# espwithDRV2880.net
KiCad netlist of a schematic drawn in EasyEDA
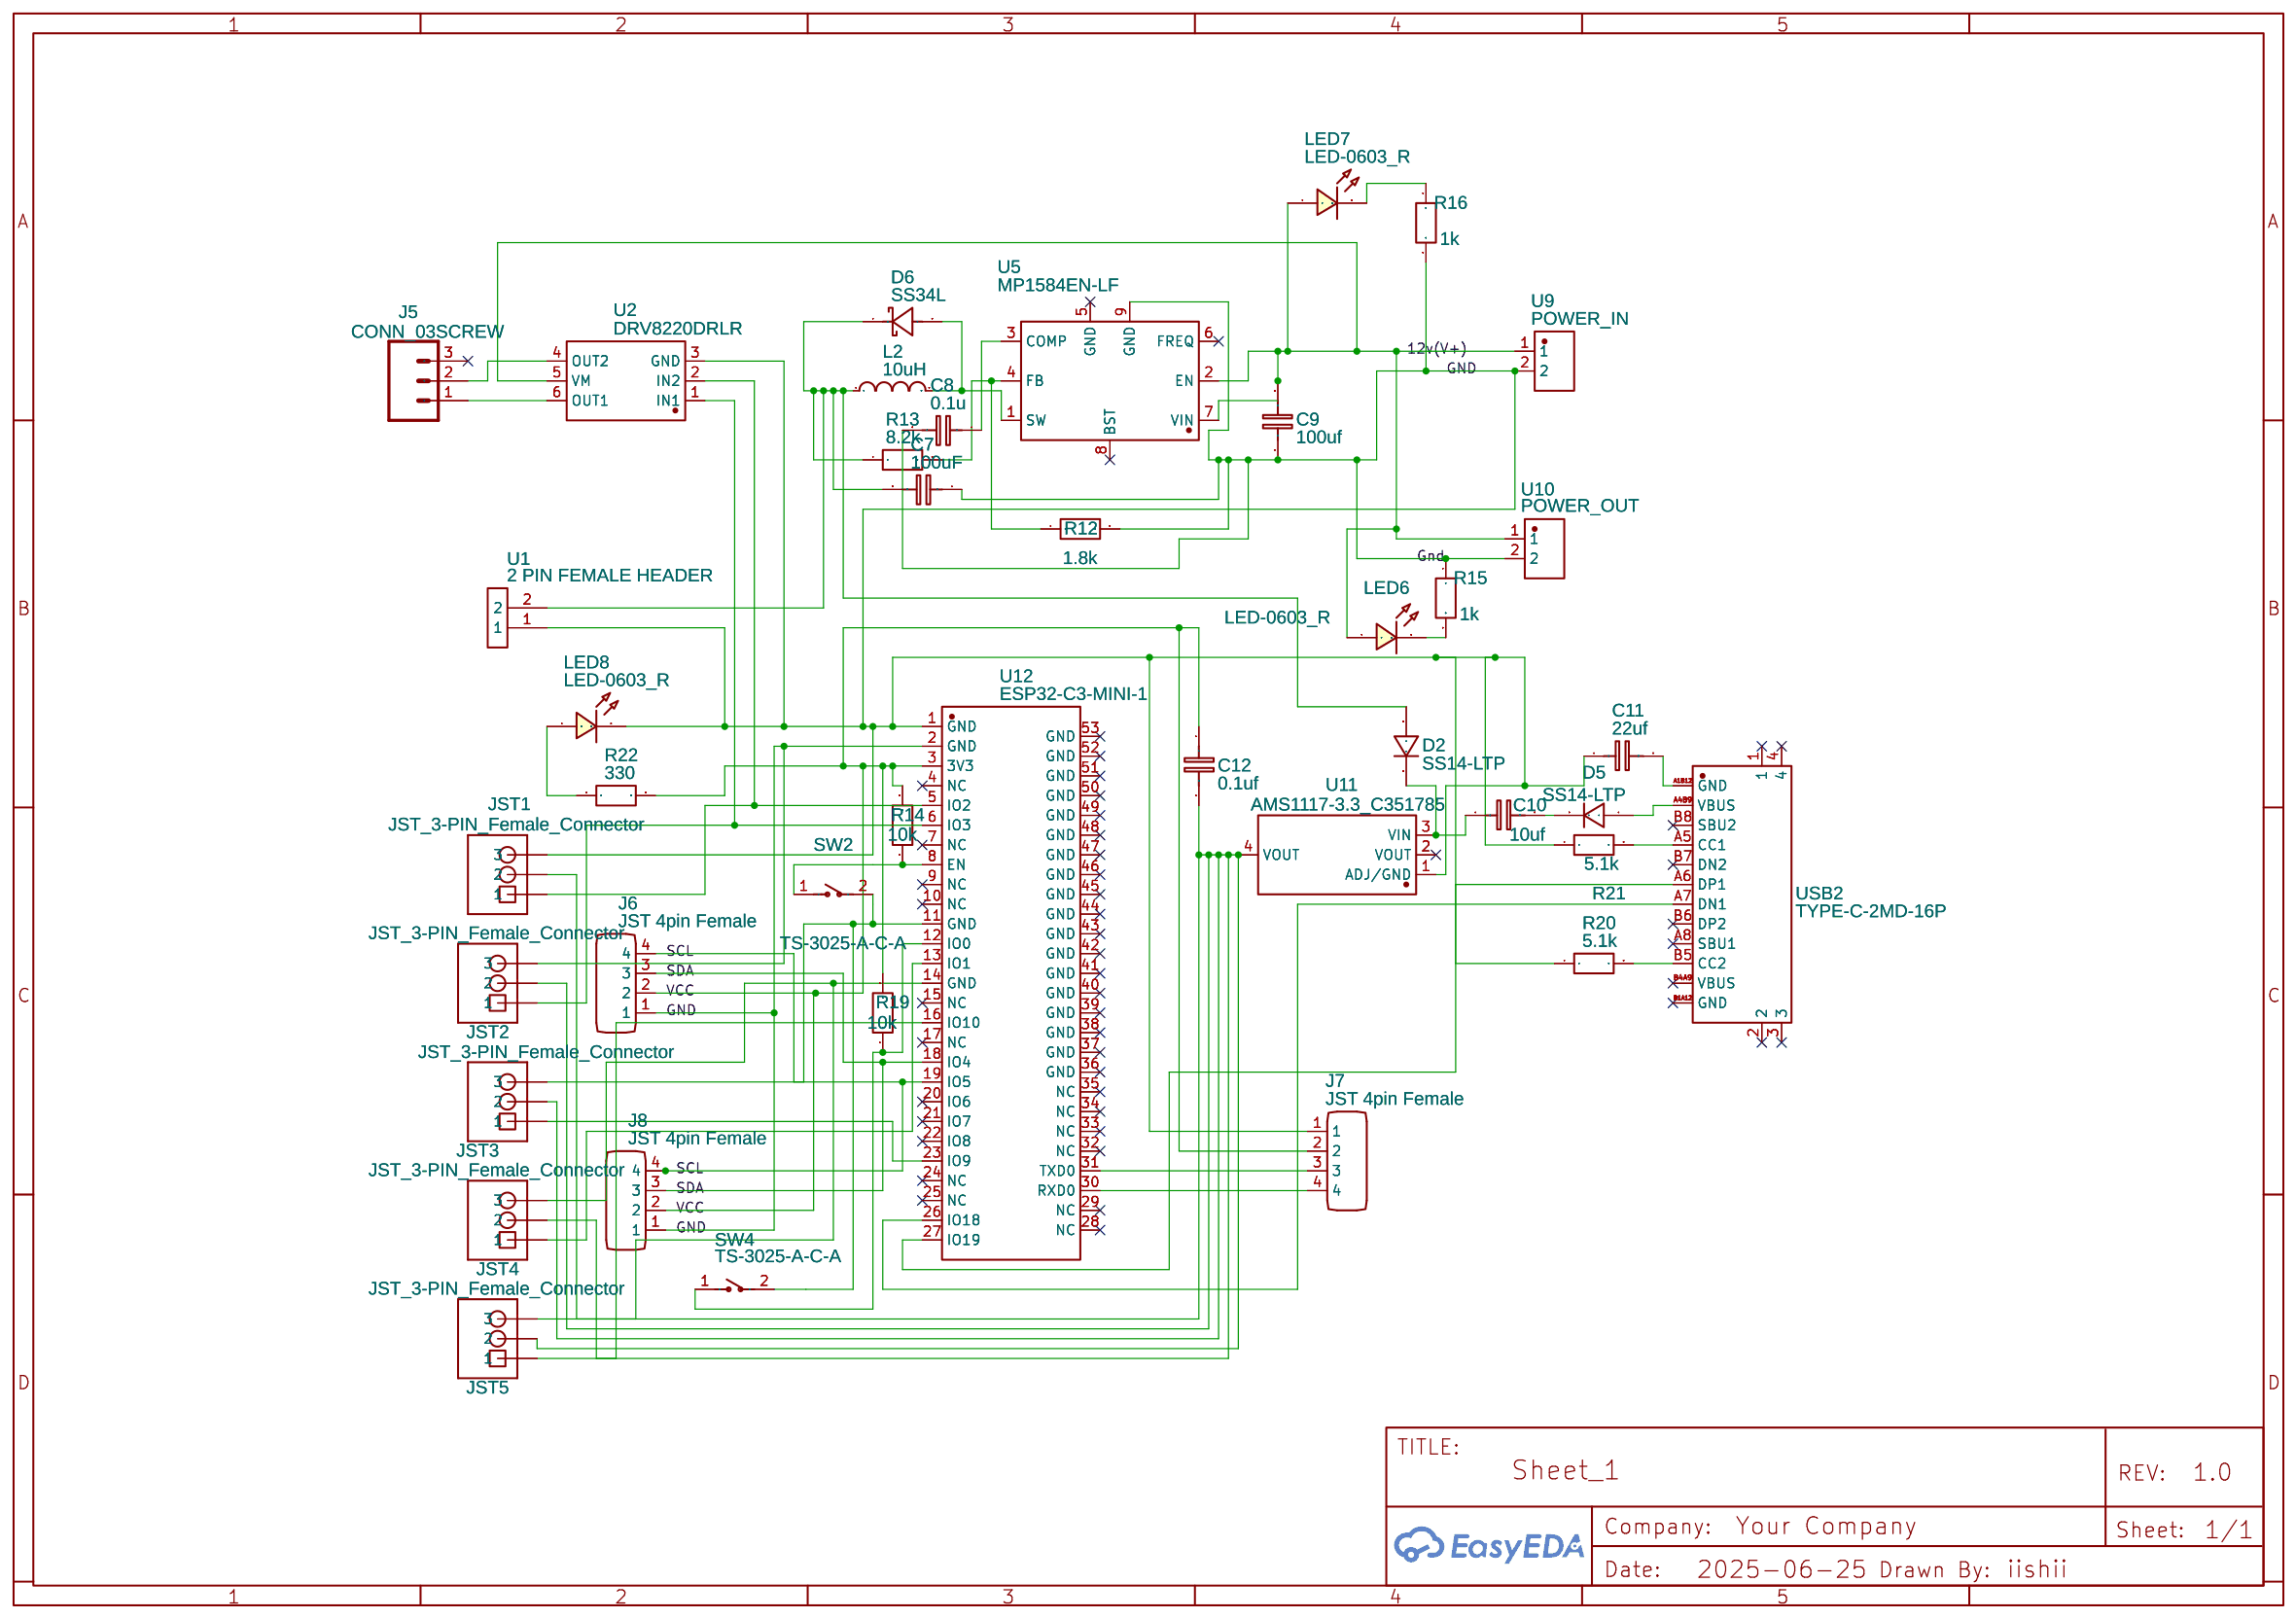
[diagram p0: schematic sheet]

(export (version "E")
  (design (tool "Eeschema 10.0.6"))
  (components
    (comp (ref "C7") (value "100uF") (libsource (lib "") (part "C_0603_EU")))
    (comp (ref "C8") (value "0.1u") (libsource (lib "") (part "C_0603_EU")))
    (comp (ref "C9") (value "100uf") (libsource (lib "") (part "C_0603_EU_2")))
    (comp (ref "C10") (value "10uf") (libsource (lib "") (part "C_0603_EU_1")))
    (comp (ref "C11") (value "22uf") (libsource (lib "") (part "C_0603_EU_1")))
    (comp (ref "C12") (value "0.1uf") (libsource (lib "") (part "C_0603_EU_3")))
    (comp (ref "D2")
      (value "SS14-LTP")
      (fields (field (name "Manufacturer") "MCC(美微科)"))
      (libsource (lib "") (part "SS14-LTP_1"))
    )
    (comp (ref "D5")
      (value "SS14-LTP")
      (fields (field (name "Manufacturer") "MCC(美微科)"))
      (libsource (lib "") (part "SS14-LTP"))
    )
    (comp (ref "D6")
      (value "SS34L")
      (fields (field (name "Manufacturer") "Hottech(合科泰)"))
      (libsource (lib "") (part "SS34L"))
    )
    (comp (ref "J5") (value "CONN_03SCREW") (libsource (lib "") (part "CONN_03SCREW")))
    (comp (ref "J6") (value "JST 4pin Female") (libsource (lib "") (part "JST 4pin Female")))
    (comp (ref "J7") (value "JST 4pin Female") (libsource (lib "") (part "JST 4pin Female_1")))
    (comp (ref "J8") (value "JST 4pin Female") (libsource (lib "") (part "JST 4pin Female")))
    (comp (ref "JST1")
      (value "JST_3-PIN_Female_Connector")
      (libsource (lib "") (part "JST_3-PIN_Female_Connector"))
    )
    (comp (ref "JST2")
      (value "JST_3-PIN_Female_Connector")
      (libsource (lib "") (part "JST_3-PIN_Female_Connector"))
    )
    (comp (ref "JST3")
      (value "JST_3-PIN_Female_Connector")
      (libsource (lib "") (part "JST_3-PIN_Female_Connector"))
    )
    (comp (ref "JST4")
      (value "JST_3-PIN_Female_Connector")
      (libsource (lib "") (part "JST_3-PIN_Female_Connector"))
    )
    (comp (ref "JST5")
      (value "JST_3-PIN_Female_Connector")
      (libsource (lib "") (part "JST_3-PIN_Female_Connector"))
    )
    (comp (ref "L2") (value "10uH") (libsource (lib "") (part "L0603_US")))
    (comp (ref "LED6")
      (value "LED-0603_R")
      (fields
        (field (name "Manufacturer Part") "19-217/R6C-AL1M2VY/3T")
        (field (name "Manufacturer") "EVERLIGHT(台湾亿光)")
      )
      (libsource (lib "") (part "LED-0603_R"))
    )
    (comp (ref "LED7")
      (value "LED-0603_R")
      (fields
        (field (name "Manufacturer Part") "19-217/R6C-AL1M2VY/3T")
        (field (name "Manufacturer") "EVERLIGHT(台湾亿光)")
      )
      (libsource (lib "") (part "LED-0603_R"))
    )
    (comp (ref "LED8")
      (value "LED-0603_R")
      (fields
        (field (name "Manufacturer Part") "19-217/R6C-AL1M2VY/3T")
        (field (name "Manufacturer") "EVERLIGHT(台湾亿光)")
      )
      (libsource (lib "") (part "LED-0603_R"))
    )
    (comp (ref "R12") (value "1.8k") (libsource (lib "") (part "R_0603_EU_2")))
    (comp (ref "R13") (value "8.2k") (libsource (lib "") (part "R_0603_EU_2")))
    (comp (ref "R14") (value "10k") (libsource (lib "") (part "R_0603_EU_1")))
    (comp (ref "R15") (value "1k") (libsource (lib "") (part "R_0603_EU")))
    (comp (ref "R16") (value "1k") (libsource (lib "") (part "R_0603_EU")))
    (comp (ref "R19") (value "10k") (libsource (lib "") (part "R_0603_EU_1")))
    (comp (ref "R20") (value "5.1k") (libsource (lib "") (part "R_0603_EU_2")))
    (comp (ref "R21") (value "5.1k") (libsource (lib "") (part "R_0603_EU_2")))
    (comp (ref "R22") (value "330") (libsource (lib "") (part "R_0603_EU_2")))
    (comp (ref "SW2")
      (value "TS-3025-A-C-A")
      (fields (field (name "Manufacturer") "XKB Connection(中国星坤)"))
      (libsource (lib "") (part "TS-3025-A-C-A"))
    )
    (comp (ref "SW4")
      (value "TS-3025-A-C-A")
      (fields (field (name "Manufacturer") "XKB Connection(中国星坤)"))
      (libsource (lib "") (part "TS-3025-A-C-A"))
    )
    (comp (ref "U1")
      (value "2 PIN FEMALE HEADER")
      (fields (field (name "Manufacturer Part") "4 Pin Female Header"))
      (libsource (lib "") (part "2 PIN FEMALE HEADER"))
    )
    (comp (ref "U2")
      (value "DRV8220DRLR")
      (fields (field (name "Manufacturer") "TI(德州仪器)"))
      (libsource (lib "") (part "DRV8220DRLR"))
    )
    (comp (ref "U5")
      (value "MP1584EN-LF")
      (fields (field (name "Manufacturer") "MPS(芯源)"))
      (libsource (lib "") (part "MP1584EN-LF"))
    )
    (comp (ref "U9")
      (value "POWER_IN")
      (fields (field (name "Manufacturer Part") "JST-B2PS-VH(LF)(SN)黑色"))
      (libsource (lib "") (part "JST-B2PS-VH(LF)(SN)黑色"))
    )
    (comp (ref "U10")
      (value "POWER_OUT")
      (fields (field (name "Manufacturer Part") "JST-B2PS-VH(LF)(SN)黑色"))
      (libsource (lib "") (part "JST-B2PS-VH(LF)(SN)黑色"))
    )
    (comp (ref "U11")
      (value "AMS1117-3.3_C351785")
      (fields (field (name "Manufacturer Part") "AMS1117-3.3") (field (name "Manufacturer") "PUOLOP(迪浦)"))
      (libsource (lib "") (part "AMS1117-3.3_C351785"))
    )
    (comp (ref "U12")
      (value "ESP32-C3-MINI-1")
      (fields (field (name "Manufacturer") "RF Crazy(智汉)"))
      (libsource (lib "") (part "ESP32-C3-MINI-1"))
    )
    (comp (ref "USB2")
      (value "TYPE-C-2MD-16P")
      (fields (field (name "Manufacturer") "JXTCONN(聚兴泰)"))
      (libsource (lib "") (part "TYPE-C-2MD-16P"))
    )
  )
  (nets
    (net (code "1") (name "/12v(V+)") (class "Default")
      (node (ref "C9") (pin "2") (pinfunction "2_2") (pintype "unspecified"))
      (node (ref "LED6") (pin "1") (pinfunction "1_1") (pintype "unspecified"))
      (node (ref "LED7") (pin "1") (pinfunction "1_1") (pintype "unspecified"))
      (node (ref "U10") (pin "1") (pinfunction "1_1") (pintype "unspecified"))
      (node (ref "U2") (pin "5") (pinfunction "VM_5") (pintype "unspecified"))
      (node (ref "U5") (pin "2") (pinfunction "EN_2") (pintype "unspecified"))
      (node (ref "U5") (pin "7") (pinfunction "VIN_7") (pintype "unspecified"))
      (node (ref "U9") (pin "1") (pinfunction "1_1") (pintype "unspecified"))
    )
    (net (code "2") (name "/GND") (class "Default")
      (node (ref "C11") (pin "1") (pinfunction "1_1") (pintype "unspecified"))
      (node (ref "C7") (pin "1") (pinfunction "1_1") (pintype "unspecified"))
      (node (ref "C8") (pin "2") (pinfunction "2_2") (pintype "unspecified"))
      (node (ref "C9") (pin "1") (pinfunction "1_1") (pintype "unspecified"))
      (node (ref "J6") (pin "1") (pinfunction "1_1") (pintype "unspecified"))
      (node (ref "J7") (pin "1") (pinfunction "1_1") (pintype "unspecified"))
      (node (ref "J8") (pin "1") (pinfunction "1_1") (pintype "unspecified"))
      (node (ref "JST1") (pin "3") (pinfunction "3_3") (pintype "unspecified"))
      (node (ref "JST2") (pin "3") (pinfunction "3_3") (pintype "unspecified"))
      (node (ref "LED8") (pin "2") (pinfunction "2_2") (pintype "unspecified"))
      (node (ref "R12") (pin "2") (pinfunction "2_2") (pintype "unspecified"))
      (node (ref "R15") (pin "1") (pinfunction "1_1") (pintype "unspecified"))
      (node (ref "R16") (pin "2") (pinfunction "2_2") (pintype "unspecified"))
      (node (ref "R20") (pin "1") (pinfunction "1_1") (pintype "unspecified"))
      (node (ref "R21") (pin "1") (pinfunction "1_1") (pintype "unspecified"))
      (node (ref "U1") (pin "1") (pinfunction "1_1") (pintype "unspecified"))
      (node (ref "U10") (pin "2") (pinfunction "2_2") (pintype "unspecified"))
      (node (ref "U11") (pin "1") (pinfunction "ADJ/GND_1") (pintype "unspecified"))
      (node (ref "U12") (pin "1") (pinfunction "GND_1") (pintype "unspecified"))
      (node (ref "U12") (pin "2") (pinfunction "GND_2") (pintype "unspecified"))
      (node (ref "U2") (pin "3") (pinfunction "GND_3") (pintype "unspecified"))
      (node (ref "U5") (pin "9") (pinfunction "GND_9") (pintype "unspecified"))
      (node (ref "U9") (pin "2") (pinfunction "2_2") (pintype "unspecified"))
    )
    (net (code "3") (name "/SCL") (class "Default")
      (node (ref "J6") (pin "4") (pinfunction "4_4") (pintype "unspecified"))
      (node (ref "J8") (pin "4") (pinfunction "4_4") (pintype "unspecified"))
      (node (ref "U12") (pin "19") (pinfunction "IO5_19") (pintype "unspecified"))
    )
    (net (code "4") (name "/SDA") (class "Default")
      (node (ref "J6") (pin "3") (pinfunction "3_3") (pintype "unspecified"))
      (node (ref "J8") (pin "3") (pinfunction "3_3") (pintype "unspecified"))
      (node (ref "U12") (pin "18") (pinfunction "IO4_18") (pintype "unspecified"))
    )
    (net (code "5") (name "/VCC") (class "Default")
      (node (ref "C12") (pin "1") (pinfunction "1_1") (pintype "unspecified"))
      (node (ref "J6") (pin "2") (pinfunction "2_2") (pintype "unspecified"))
      (node (ref "J7") (pin "2") (pinfunction "2_2") (pintype "unspecified"))
      (node (ref "J8") (pin "2") (pinfunction "2_2") (pintype "unspecified"))
      (node (ref "R14") (pin "2") (pinfunction "2_2") (pintype "unspecified"))
      (node (ref "R19") (pin "2") (pinfunction "2_2") (pintype "unspecified"))
      (node (ref "R22") (pin "2") (pinfunction "2_2") (pintype "unspecified"))
      (node (ref "U12") (pin "3") (pinfunction "3V3_3") (pintype "unspecified"))
    )
    (net (code "6") (name "Net-(C11-Pad2)") (class "Default")
      (node (ref "C11") (pin "2") (pinfunction "2_2") (pintype "unspecified"))
      (node (ref "USB2") (pin "A1B12") (pinfunction "GND_A1B12") (pintype "unspecified"))
    )
    (net (code "7") (name "Net-(C12-Pad2)") (class "Default")
      (node (ref "C12") (pin "2") (pinfunction "2_2") (pintype "unspecified"))
      (node (ref "JST1") (pin "2") (pinfunction "2_2") (pintype "unspecified"))
      (node (ref "JST2") (pin "2") (pinfunction "2_2") (pintype "unspecified"))
      (node (ref "JST3") (pin "2") (pinfunction "2_2") (pintype "unspecified"))
      (node (ref "JST4") (pin "2") (pinfunction "2_2") (pintype "unspecified"))
      (node (ref "JST5") (pin "2") (pinfunction "2_2") (pintype "unspecified"))
      (node (ref "U11") (pin "4") (pinfunction "VOUT_4") (pintype "unspecified"))
    )
    (net (code "8") (name "Net-(D2-A)") (class "Default")
      (node (ref "C7") (pin "2") (pinfunction "2_2") (pintype "unspecified"))
      (node (ref "D2") (pin "1") (pinfunction "A_1") (pintype "unspecified"))
      (node (ref "D6") (pin "1") (pinfunction "C_1") (pintype "unspecified"))
      (node (ref "L2") (pin "1") (pinfunction "1_1") (pintype "unspecified"))
      (node (ref "R13") (pin "1") (pinfunction "1_1") (pintype "unspecified"))
      (node (ref "U1") (pin "2") (pinfunction "2_2") (pintype "unspecified"))
    )
    (net (code "9") (name "Net-(D2-K)") (class "Default")
      (node (ref "C10") (pin "1") (pinfunction "1_1") (pintype "unspecified"))
      (node (ref "D2") (pin "2") (pinfunction "K_2") (pintype "unspecified"))
      (node (ref "U11") (pin "3") (pinfunction "VIN_3") (pintype "unspecified"))
    )
    (net (code "10") (name "Net-(D5-A)") (class "Default")
      (node (ref "D5") (pin "1") (pinfunction "A_1") (pintype "unspecified"))
      (node (ref "USB2") (pin "A4B9") (pinfunction "VBUS_A4B9") (pintype "unspecified"))
    )
    (net (code "11") (name "Net-(D5-K)") (class "Default")
      (node (ref "C10") (pin "2") (pinfunction "2_2") (pintype "unspecified"))
      (node (ref "D5") (pin "2") (pinfunction "K_2") (pintype "unspecified"))
    )
    (net (code "12") (name "Net-(D6-A)") (class "Default")
      (node (ref "D6") (pin "2") (pinfunction "A_2") (pintype "unspecified"))
      (node (ref "L2") (pin "2") (pinfunction "2_2") (pintype "unspecified"))
      (node (ref "U5") (pin "1") (pinfunction "SW_1") (pintype "unspecified"))
    )
    (net (code "13") (name "Net-(JST3-Pad3)") (class "Default")
      (node (ref "JST3") (pin "3") (pinfunction "3_3") (pintype "unspecified"))
      (node (ref "SW2") (pin "2") (pinfunction "2_2") (pintype "unspecified"))
      (node (ref "SW4") (pin "2") (pinfunction "2_2") (pintype "unspecified"))
      (node (ref "U12") (pin "11") (pinfunction "GND_11") (pintype "unspecified"))
    )
    (net (code "14") (name "Net-(JST4-Pad3)") (class "Default")
      (node (ref "JST4") (pin "3") (pinfunction "3_3") (pintype "unspecified"))
      (node (ref "JST5") (pin "3") (pinfunction "3_3") (pintype "unspecified"))
      (node (ref "U12") (pin "14") (pinfunction "GND_14") (pintype "unspecified"))
    )
    (net (code "15") (name "Net-(LED6-Pad2)") (class "Default")
      (node (ref "LED6") (pin "2") (pinfunction "2_2") (pintype "unspecified"))
      (node (ref "R15") (pin "2") (pinfunction "2_2") (pintype "unspecified"))
    )
    (net (code "16") (name "Net-(LED7-Pad2)") (class "Default")
      (node (ref "LED7") (pin "2") (pinfunction "2_2") (pintype "unspecified"))
      (node (ref "R16") (pin "1") (pinfunction "1_1") (pintype "unspecified"))
    )
    (net (code "17") (name "Net-(LED8-Pad1)") (class "Default")
      (node (ref "LED8") (pin "1") (pinfunction "1_1") (pintype "unspecified"))
      (node (ref "R22") (pin "1") (pinfunction "1_1") (pintype "unspecified"))
    )
    (net (code "18") (name "Net-(U2-OUT1)") (class "Default")
      (node (ref "J5") (pin "1") (pinfunction "1_1") (pintype "bidirectional"))
      (node (ref "U2") (pin "6") (pinfunction "OUT1_6") (pintype "unspecified"))
    )
    (net (code "19") (name "Net-(U2-OUT2)") (class "Default")
      (node (ref "J5") (pin "2") (pinfunction "2_2") (pintype "bidirectional"))
      (node (ref "U2") (pin "4") (pinfunction "OUT2_4") (pintype "unspecified"))
    )
    (net (code "20") (name "Net-(U5-COMP)") (class "Default")
      (node (ref "C8") (pin "1") (pinfunction "1_1") (pintype "unspecified"))
      (node (ref "U5") (pin "3") (pinfunction "COMP_3") (pintype "unspecified"))
    )
    (net (code "21") (name "Net-(U5-FB)") (class "Default")
      (node (ref "R12") (pin "1") (pinfunction "1_1") (pintype "unspecified"))
      (node (ref "R13") (pin "2") (pinfunction "2_2") (pintype "unspecified"))
      (node (ref "U5") (pin "4") (pinfunction "FB_4") (pintype "unspecified"))
    )
    (net (code "22") (name "Net-(U12-EN)") (class "Default")
      (node (ref "R14") (pin "1") (pinfunction "1_1") (pintype "unspecified"))
      (node (ref "SW2") (pin "1") (pinfunction "1_1") (pintype "unspecified"))
      (node (ref "U12") (pin "8") (pinfunction "EN_8") (pintype "unspecified"))
    )
    (net (code "23") (name "Net-(U12-IO0)") (class "Default")
      (node (ref "R19") (pin "1") (pinfunction "1_1") (pintype "unspecified"))
      (node (ref "SW4") (pin "1") (pinfunction "1_1") (pintype "unspecified"))
      (node (ref "U12") (pin "12") (pinfunction "IO0_12") (pintype "unspecified"))
    )
    (net (code "24") (name "Net-(U12-IO1)") (class "Default")
      (node (ref "JST4") (pin "1") (pinfunction "1_1") (pintype "unspecified"))
      (node (ref "U12") (pin "13") (pinfunction "IO1_13") (pintype "unspecified"))
    )
    (net (code "25") (name "Net-(U12-IO2)") (class "Default")
      (node (ref "JST1") (pin "1") (pinfunction "1_1") (pintype "unspecified"))
      (node (ref "U12") (pin "5") (pinfunction "IO2_5") (pintype "unspecified"))
      (node (ref "U2") (pin "2") (pinfunction "IN2_2") (pintype "unspecified"))
    )
    (net (code "26") (name "Net-(U12-IO3)") (class "Default")
      (node (ref "JST2") (pin "1") (pinfunction "1_1") (pintype "unspecified"))
      (node (ref "U12") (pin "6") (pinfunction "IO3_6") (pintype "unspecified"))
      (node (ref "U2") (pin "1") (pinfunction "IN1_1") (pintype "unspecified"))
    )
    (net (code "27") (name "Net-(U12-IO9)") (class "Default")
      (node (ref "JST3") (pin "1") (pinfunction "1_1") (pintype "unspecified"))
      (node (ref "U12") (pin "23") (pinfunction "IO9_23") (pintype "unspecified"))
    )
    (net (code "28") (name "Net-(U12-IO10)") (class "Default")
      (node (ref "JST5") (pin "1") (pinfunction "1_1") (pintype "unspecified"))
      (node (ref "U12") (pin "16") (pinfunction "IO10_16") (pintype "unspecified"))
    )
    (net (code "29") (name "Net-(U12-IO18)") (class "Default")
      (node (ref "U12") (pin "26") (pinfunction "IO18_26") (pintype "unspecified"))
      (node (ref "USB2") (pin "A7") (pinfunction "DN1_A7") (pintype "unspecified"))
    )
    (net (code "30") (name "Net-(U12-IO19)") (class "Default")
      (node (ref "U12") (pin "27") (pinfunction "IO19_27") (pintype "unspecified"))
      (node (ref "USB2") (pin "A6") (pinfunction "DP1_A6") (pintype "unspecified"))
    )
    (net (code "31") (name "Net-(U12-RXD0)") (class "Default")
      (node (ref "J7") (pin "4") (pinfunction "4_4") (pintype "unspecified"))
      (node (ref "U12") (pin "30") (pinfunction "RXD0_30") (pintype "unspecified"))
    )
    (net (code "32") (name "Net-(U12-TXD0)") (class "Default")
      (node (ref "J7") (pin "3") (pinfunction "3_3") (pintype "unspecified"))
      (node (ref "U12") (pin "31") (pinfunction "TXD0_31") (pintype "unspecified"))
    )
    (net (code "33") (name "Net-(USB2-CC1)") (class "Default")
      (node (ref "R21") (pin "2") (pinfunction "2_2") (pintype "unspecified"))
      (node (ref "USB2") (pin "A5") (pinfunction "CC1_A5") (pintype "unspecified"))
    )
    (net (code "34") (name "Net-(USB2-CC2)") (class "Default")
      (node (ref "R20") (pin "2") (pinfunction "2_2") (pintype "unspecified"))
      (node (ref "USB2") (pin "B5") (pinfunction "CC2_B5") (pintype "unspecified"))
    )
    (net (code "35") (name "unconnected-(J5-Pad3)") (class "Default")
      (node (ref "J5") (pin "3") (pinfunction "3_3") (pintype "bidirectional+no_connect"))
    )
    (net (code "36") (name "unconnected-(U5-BST-Pad8)") (class "Default")
      (node (ref "U5") (pin "8") (pinfunction "BST_8") (pintype "unspecified+no_connect"))
    )
    (net (code "37") (name "unconnected-(U5-FREQ-Pad6)") (class "Default")
      (node (ref "U5") (pin "6") (pinfunction "FREQ_6") (pintype "unspecified+no_connect"))
    )
    (net (code "38") (name "unconnected-(U5-GND-Pad5)") (class "Default")
      (node (ref "U5") (pin "5") (pinfunction "GND_5") (pintype "unspecified+no_connect"))
    )
    (net (code "39") (name "unconnected-(U11-VOUT-Pad2)") (class "Default")
      (node (ref "U11") (pin "2") (pinfunction "VOUT_2") (pintype "unspecified+no_connect"))
    )
    (net (code "40") (name "unconnected-(U12-GND-Pad36)") (class "Default")
      (node (ref "U12") (pin "36") (pinfunction "GND_36") (pintype "unspecified+no_connect"))
    )
    (net (code "41") (name "unconnected-(U12-GND-Pad37)") (class "Default")
      (node (ref "U12") (pin "37") (pinfunction "GND_37") (pintype "unspecified+no_connect"))
    )
    (net (code "42") (name "unconnected-(U12-GND-Pad38)") (class "Default")
      (node (ref "U12") (pin "38") (pinfunction "GND_38") (pintype "unspecified+no_connect"))
    )
    (net (code "43") (name "unconnected-(U12-GND-Pad39)") (class "Default")
      (node (ref "U12") (pin "39") (pinfunction "GND_39") (pintype "unspecified+no_connect"))
    )
    (net (code "44") (name "unconnected-(U12-GND-Pad40)") (class "Default")
      (node (ref "U12") (pin "40") (pinfunction "GND_40") (pintype "unspecified+no_connect"))
    )
    (net (code "45") (name "unconnected-(U12-GND-Pad41)") (class "Default")
      (node (ref "U12") (pin "41") (pinfunction "GND_41") (pintype "unspecified+no_connect"))
    )
    (net (code "46") (name "unconnected-(U12-GND-Pad42)") (class "Default")
      (node (ref "U12") (pin "42") (pinfunction "GND_42") (pintype "unspecified+no_connect"))
    )
    (net (code "47") (name "unconnected-(U12-GND-Pad43)") (class "Default")
      (node (ref "U12") (pin "43") (pinfunction "GND_43") (pintype "unspecified+no_connect"))
    )
    (net (code "48") (name "unconnected-(U12-GND-Pad44)") (class "Default")
      (node (ref "U12") (pin "44") (pinfunction "GND_44") (pintype "unspecified+no_connect"))
    )
    (net (code "49") (name "unconnected-(U12-GND-Pad45)") (class "Default")
      (node (ref "U12") (pin "45") (pinfunction "GND_45") (pintype "unspecified+no_connect"))
    )
    (net (code "50") (name "unconnected-(U12-GND-Pad46)") (class "Default")
      (node (ref "U12") (pin "46") (pinfunction "GND_46") (pintype "unspecified+no_connect"))
    )
    (net (code "51") (name "unconnected-(U12-GND-Pad47)") (class "Default")
      (node (ref "U12") (pin "47") (pinfunction "GND_47") (pintype "unspecified+no_connect"))
    )
    (net (code "52") (name "unconnected-(U12-GND-Pad48)") (class "Default")
      (node (ref "U12") (pin "48") (pinfunction "GND_48") (pintype "unspecified+no_connect"))
    )
    (net (code "53") (name "unconnected-(U12-GND-Pad49)") (class "Default")
      (node (ref "U12") (pin "49") (pinfunction "GND_49") (pintype "unspecified+no_connect"))
    )
    (net (code "54") (name "unconnected-(U12-GND-Pad50)") (class "Default")
      (node (ref "U12") (pin "50") (pinfunction "GND_50") (pintype "unspecified+no_connect"))
    )
    (net (code "55") (name "unconnected-(U12-GND-Pad51)") (class "Default")
      (node (ref "U12") (pin "51") (pinfunction "GND_51") (pintype "unspecified+no_connect"))
    )
    (net (code "56") (name "unconnected-(U12-GND-Pad52)") (class "Default")
      (node (ref "U12") (pin "52") (pinfunction "GND_52") (pintype "unspecified+no_connect"))
    )
    (net (code "57") (name "unconnected-(U12-GND-Pad53)") (class "Default")
      (node (ref "U12") (pin "53") (pinfunction "GND_53") (pintype "unspecified+no_connect"))
    )
    (net (code "58") (name "unconnected-(U12-IO6-Pad20)") (class "Default")
      (node (ref "U12") (pin "20") (pinfunction "IO6_20") (pintype "unspecified+no_connect"))
    )
    (net (code "59") (name "unconnected-(U12-IO7-Pad21)") (class "Default")
      (node (ref "U12") (pin "21") (pinfunction "IO7_21") (pintype "unspecified+no_connect"))
    )
    (net (code "60") (name "unconnected-(U12-IO8-Pad22)") (class "Default")
      (node (ref "U12") (pin "22") (pinfunction "IO8_22") (pintype "unspecified+no_connect"))
    )
    (net (code "61") (name "unconnected-(U12-NC-Pad4)") (class "Default")
      (node (ref "U12") (pin "4") (pinfunction "NC_4") (pintype "unspecified+no_connect"))
    )
    (net (code "62") (name "unconnected-(U12-NC-Pad7)") (class "Default")
      (node (ref "U12") (pin "7") (pinfunction "NC_7") (pintype "unspecified+no_connect"))
    )
    (net (code "63") (name "unconnected-(U12-NC-Pad9)") (class "Default")
      (node (ref "U12") (pin "9") (pinfunction "NC_9") (pintype "unspecified+no_connect"))
    )
    (net (code "64") (name "unconnected-(U12-NC-Pad10)") (class "Default")
      (node (ref "U12") (pin "10") (pinfunction "NC_10") (pintype "unspecified+no_connect"))
    )
    (net (code "65") (name "unconnected-(U12-NC-Pad15)") (class "Default")
      (node (ref "U12") (pin "15") (pinfunction "NC_15") (pintype "unspecified+no_connect"))
    )
    (net (code "66") (name "unconnected-(U12-NC-Pad17)") (class "Default")
      (node (ref "U12") (pin "17") (pinfunction "NC_17") (pintype "unspecified+no_connect"))
    )
    (net (code "67") (name "unconnected-(U12-NC-Pad24)") (class "Default")
      (node (ref "U12") (pin "24") (pinfunction "NC_24") (pintype "unspecified+no_connect"))
    )
    (net (code "68") (name "unconnected-(U12-NC-Pad25)") (class "Default")
      (node (ref "U12") (pin "25") (pinfunction "NC_25") (pintype "unspecified+no_connect"))
    )
    (net (code "69") (name "unconnected-(U12-NC-Pad28)") (class "Default")
      (node (ref "U12") (pin "28") (pinfunction "NC_28") (pintype "unspecified+no_connect"))
    )
    (net (code "70") (name "unconnected-(U12-NC-Pad29)") (class "Default")
      (node (ref "U12") (pin "29") (pinfunction "NC_29") (pintype "unspecified+no_connect"))
    )
    (net (code "71") (name "unconnected-(U12-NC-Pad32)") (class "Default")
      (node (ref "U12") (pin "32") (pinfunction "NC_32") (pintype "unspecified+no_connect"))
    )
    (net (code "72") (name "unconnected-(U12-NC-Pad33)") (class "Default")
      (node (ref "U12") (pin "33") (pinfunction "NC_33") (pintype "unspecified+no_connect"))
    )
    (net (code "73") (name "unconnected-(U12-NC-Pad34)") (class "Default")
      (node (ref "U12") (pin "34") (pinfunction "NC_34") (pintype "unspecified+no_connect"))
    )
    (net (code "74") (name "unconnected-(U12-NC-Pad35)") (class "Default")
      (node (ref "U12") (pin "35") (pinfunction "NC_35") (pintype "unspecified+no_connect"))
    )
    (net (code "75") (name "unconnected-(USB2-DN2-PadB7)") (class "Default")
      (node (ref "USB2") (pin "B7") (pinfunction "DN2_B7") (pintype "unspecified+no_connect"))
    )
    (net (code "76") (name "unconnected-(USB2-DP2-PadB6)") (class "Default")
      (node (ref "USB2") (pin "B6") (pinfunction "DP2_B6") (pintype "unspecified+no_connect"))
    )
    (net (code "77") (name "unconnected-(USB2-GND-PadB1A12)") (class "Default")
      (node (ref "USB2") (pin "B1A12") (pinfunction "GND_B1A12") (pintype "unspecified+no_connect"))
    )
    (net (code "78") (name "unconnected-(USB2-Pad1)") (class "Default")
      (node (ref "USB2") (pin "1") (pinfunction "1_1") (pintype "unspecified+no_connect"))
    )
    (net (code "79") (name "unconnected-(USB2-Pad2)") (class "Default")
      (node (ref "USB2") (pin "2") (pinfunction "2_2") (pintype "unspecified+no_connect"))
    )
    (net (code "80") (name "unconnected-(USB2-Pad3)") (class "Default")
      (node (ref "USB2") (pin "3") (pinfunction "3_3") (pintype "unspecified+no_connect"))
    )
    (net (code "81") (name "unconnected-(USB2-Pad4)") (class "Default")
      (node (ref "USB2") (pin "4") (pinfunction "4_4") (pintype "unspecified+no_connect"))
    )
    (net (code "82") (name "unconnected-(USB2-SBU1-PadA8)") (class "Default")
      (node (ref "USB2") (pin "A8") (pinfunction "SBU1_A8") (pintype "unspecified+no_connect"))
    )
    (net (code "83") (name "unconnected-(USB2-SBU2-PadB8)") (class "Default")
      (node (ref "USB2") (pin "B8") (pinfunction "SBU2_B8") (pintype "unspecified+no_connect"))
    )
    (net (code "84") (name "unconnected-(USB2-VBUS-PadB4A9)") (class "Default")
      (node (ref "USB2") (pin "B4A9") (pinfunction "VBUS_B4A9") (pintype "unspecified+no_connect"))
    )
  )
)
